# Sensor_board_V_1_0.net
KiCad netlist of a schematic drawn in EAGLE
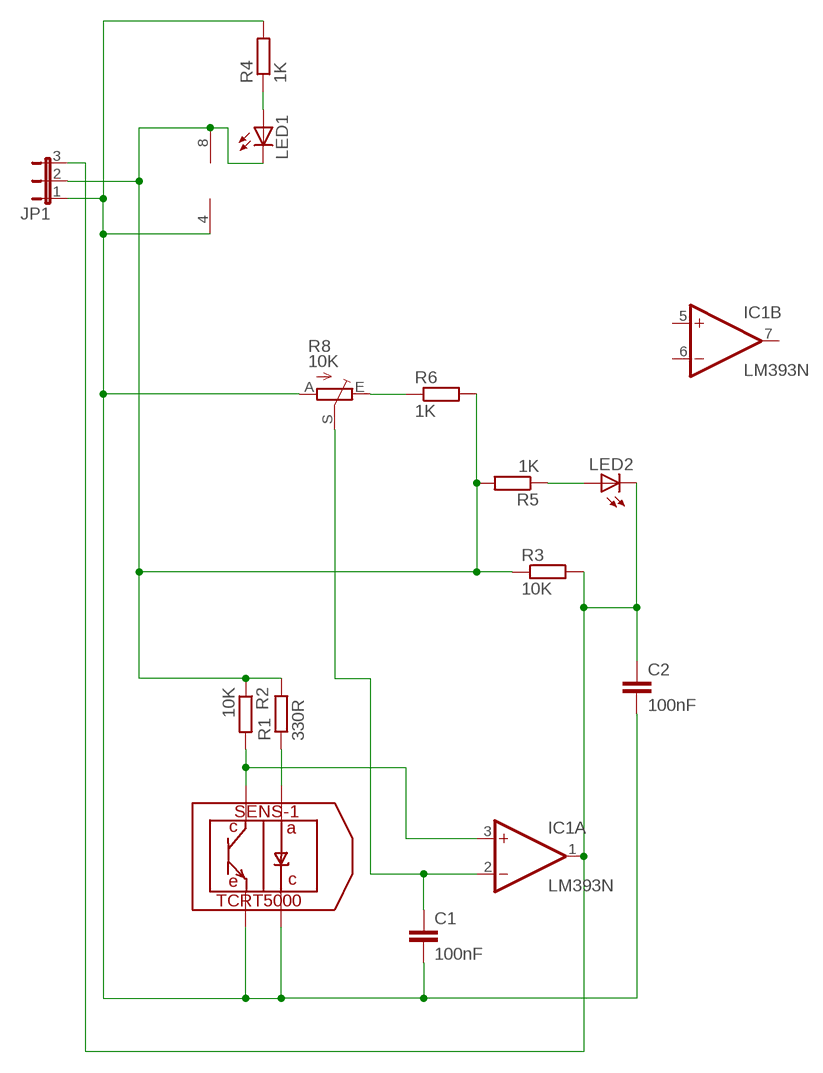
[diagram p0: schematic, sheet 1]

(export (version "E")
  (design (tool "Eeschema 10.0.6"))
  (components
    (comp (ref "C1")
      (value "100nF")
      (footprint "eagle-import:C025_050-025X075")
      (libsource (lib "eagle-import") (part "C-EU025_050-025X075"))
    )
    (comp (ref "C2")
      (value "100nF")
      (footprint "eagle-import:C025_050-025X075")
      (libsource (lib "eagle-import") (part "C-EU025_050-025X075"))
    )
    (comp (ref "IC1")
      (value "LM393N")
      (footprint "eagle-import:DIL08")
      (libsource (lib "eagle-import") (part "LM393N"))
    )
    (comp (ref "JP1")
      (value "JP2E")
      (footprint "eagle-import:JP2")
      (libsource (lib "eagle-import") (part "JP2E"))
    )
    (comp (ref "LED1")
      (value "LED3MM")
      (footprint "eagle-import:LED3MM")
      (libsource (lib "eagle-import") (part "LED3MM"))
    )
    (comp (ref "LED2")
      (value "LED3MM")
      (footprint "eagle-import:LED3MM")
      (libsource (lib "eagle-import") (part "LED3MM"))
    )
    (comp (ref "R1")
      (value "330R")
      (footprint "eagle-import:0309_10")
      (libsource (lib "eagle-import") (part "R-EU_0309/10"))
    )
    (comp (ref "R2")
      (value "10K")
      (footprint "eagle-import:0309_10")
      (libsource (lib "eagle-import") (part "R-EU_0309/10"))
    )
    (comp (ref "R3")
      (value "10K")
      (footprint "eagle-import:0309_10")
      (libsource (lib "eagle-import") (part "R-EU_0309/10"))
    )
    (comp (ref "R4")
      (value "1K")
      (footprint "eagle-import:0309_10")
      (libsource (lib "eagle-import") (part "R-EU_0309/10"))
    )
    (comp (ref "R5")
      (value "1K")
      (footprint "eagle-import:0309_10")
      (libsource (lib "eagle-import") (part "R-EU_0309/10"))
    )
    (comp (ref "R6")
      (value "1K")
      (footprint "eagle-import:0309_10")
      (libsource (lib "eagle-import") (part "R-EU_0309/10"))
    )
    (comp (ref "R8")
      (value "10K")
      (footprint "eagle-import:B64Y")
      (libsource (lib "eagle-import") (part "TRIM_EU-B64Y"))
    )
    (comp (ref "SENS-1")
      (value "TCRT5000")
      (footprint "eagle-import:5000")
      (libsource (lib "eagle-import") (part "TCRT5000"))
    )
  )
  (nets
    (net (code "1") (name "Net-(IC1A-+IN)") (class "Default")
      (node (ref "IC1") (pin "3") (pinfunction "+IN_3") (pintype "input"))
      (node (ref "R2") (pin "2") (pinfunction "2_2") (pintype "passive"))
      (node (ref "SENS-1") (pin "P$1") (pinfunction "P$1_P$1") (pintype "passive"))
    )
    (net (code "2") (name "Net-(IC1A--IN)") (class "Default")
      (node (ref "C1") (pin "1") (pinfunction "1_1") (pintype "passive"))
      (node (ref "IC1") (pin "2") (pinfunction "-IN_2") (pintype "input"))
      (node (ref "R8") (pin "S") (pinfunction "S_S") (pintype "passive"))
    )
    (net (code "3") (name "Net-(IC1A-OUT)") (class "Default")
      (node (ref "C2") (pin "1") (pinfunction "1_1") (pintype "passive"))
      (node (ref "IC1") (pin "1") (pinfunction "OUT_1") (pintype "output"))
      (node (ref "JP1") (pin "3") (pinfunction "3_3") (pintype "passive"))
      (node (ref "LED2") (pin "K") (pinfunction "C_K") (pintype "passive"))
      (node (ref "R3") (pin "2") (pinfunction "2_2") (pintype "passive"))
    )
    (net (code "4") (name "Net-(IC1C-V+)") (class "Default")
      (node (ref "IC1") (pin "8") (pinfunction "V+_8") (pintype "power_in"))
      (node (ref "JP1") (pin "2") (pinfunction "2_2") (pintype "passive"))
      (node (ref "LED1") (pin "K") (pinfunction "C_K") (pintype "passive"))
      (node (ref "R1") (pin "2") (pinfunction "2_2") (pintype "passive"))
      (node (ref "R2") (pin "1") (pinfunction "1_1") (pintype "passive"))
      (node (ref "R3") (pin "1") (pinfunction "1_1") (pintype "passive"))
      (node (ref "R5") (pin "2") (pinfunction "2_2") (pintype "passive"))
      (node (ref "R6") (pin "2") (pinfunction "2_2") (pintype "passive"))
    )
    (net (code "5") (name "Net-(IC1C-V-)") (class "Default")
      (node (ref "C1") (pin "2") (pinfunction "2_2") (pintype "passive"))
      (node (ref "C2") (pin "2") (pinfunction "2_2") (pintype "passive"))
      (node (ref "IC1") (pin "4") (pinfunction "V-_4") (pintype "power_in"))
      (node (ref "JP1") (pin "1") (pinfunction "1_1") (pintype "passive"))
      (node (ref "R4") (pin "2") (pinfunction "2_2") (pintype "passive"))
      (node (ref "R8") (pin "A") (pinfunction "A_A") (pintype "passive"))
      (node (ref "SENS-1") (pin "P$2") (pinfunction "P$2_P$2") (pintype "passive"))
      (node (ref "SENS-1") (pin "P$4") (pinfunction "P$4_P$4") (pintype "passive"))
    )
    (net (code "6") (name "Net-(LED1-PadA)") (class "Default")
      (node (ref "LED1") (pin "A") (pinfunction "A_A") (pintype "passive"))
      (node (ref "R4") (pin "1") (pinfunction "1_1") (pintype "passive"))
    )
    (net (code "7") (name "Net-(LED2-PadA)") (class "Default")
      (node (ref "LED2") (pin "A") (pinfunction "A_A") (pintype "passive"))
      (node (ref "R5") (pin "1") (pinfunction "1_1") (pintype "passive"))
    )
    (net (code "8") (name "Net-(R1-Pad1)") (class "Default")
      (node (ref "R1") (pin "1") (pinfunction "1_1") (pintype "passive"))
      (node (ref "SENS-1") (pin "P$3") (pinfunction "P$3_P$3") (pintype "passive"))
    )
    (net (code "9") (name "Net-(R6-Pad1)") (class "Default")
      (node (ref "R6") (pin "1") (pinfunction "1_1") (pintype "passive"))
      (node (ref "R8") (pin "E") (pinfunction "E_E") (pintype "passive"))
    )
    (net (code "10") (name "unconnected-(IC1B-+IN-Pad5)") (class "Default")
      (node (ref "IC1") (pin "5") (pinfunction "+IN_5") (pintype "input"))
    )
    (net (code "11") (name "unconnected-(IC1B--IN-Pad6)") (class "Default")
      (node (ref "IC1") (pin "6") (pinfunction "-IN_6") (pintype "input"))
    )
    (net (code "12") (name "unconnected-(IC1B-OUT-Pad7)") (class "Default")
      (node (ref "IC1") (pin "7") (pinfunction "OUT_7") (pintype "output"))
    )
  )
)
